# MCP794x-breakout.net
KiCad netlist of a schematic drawn in EAGLE
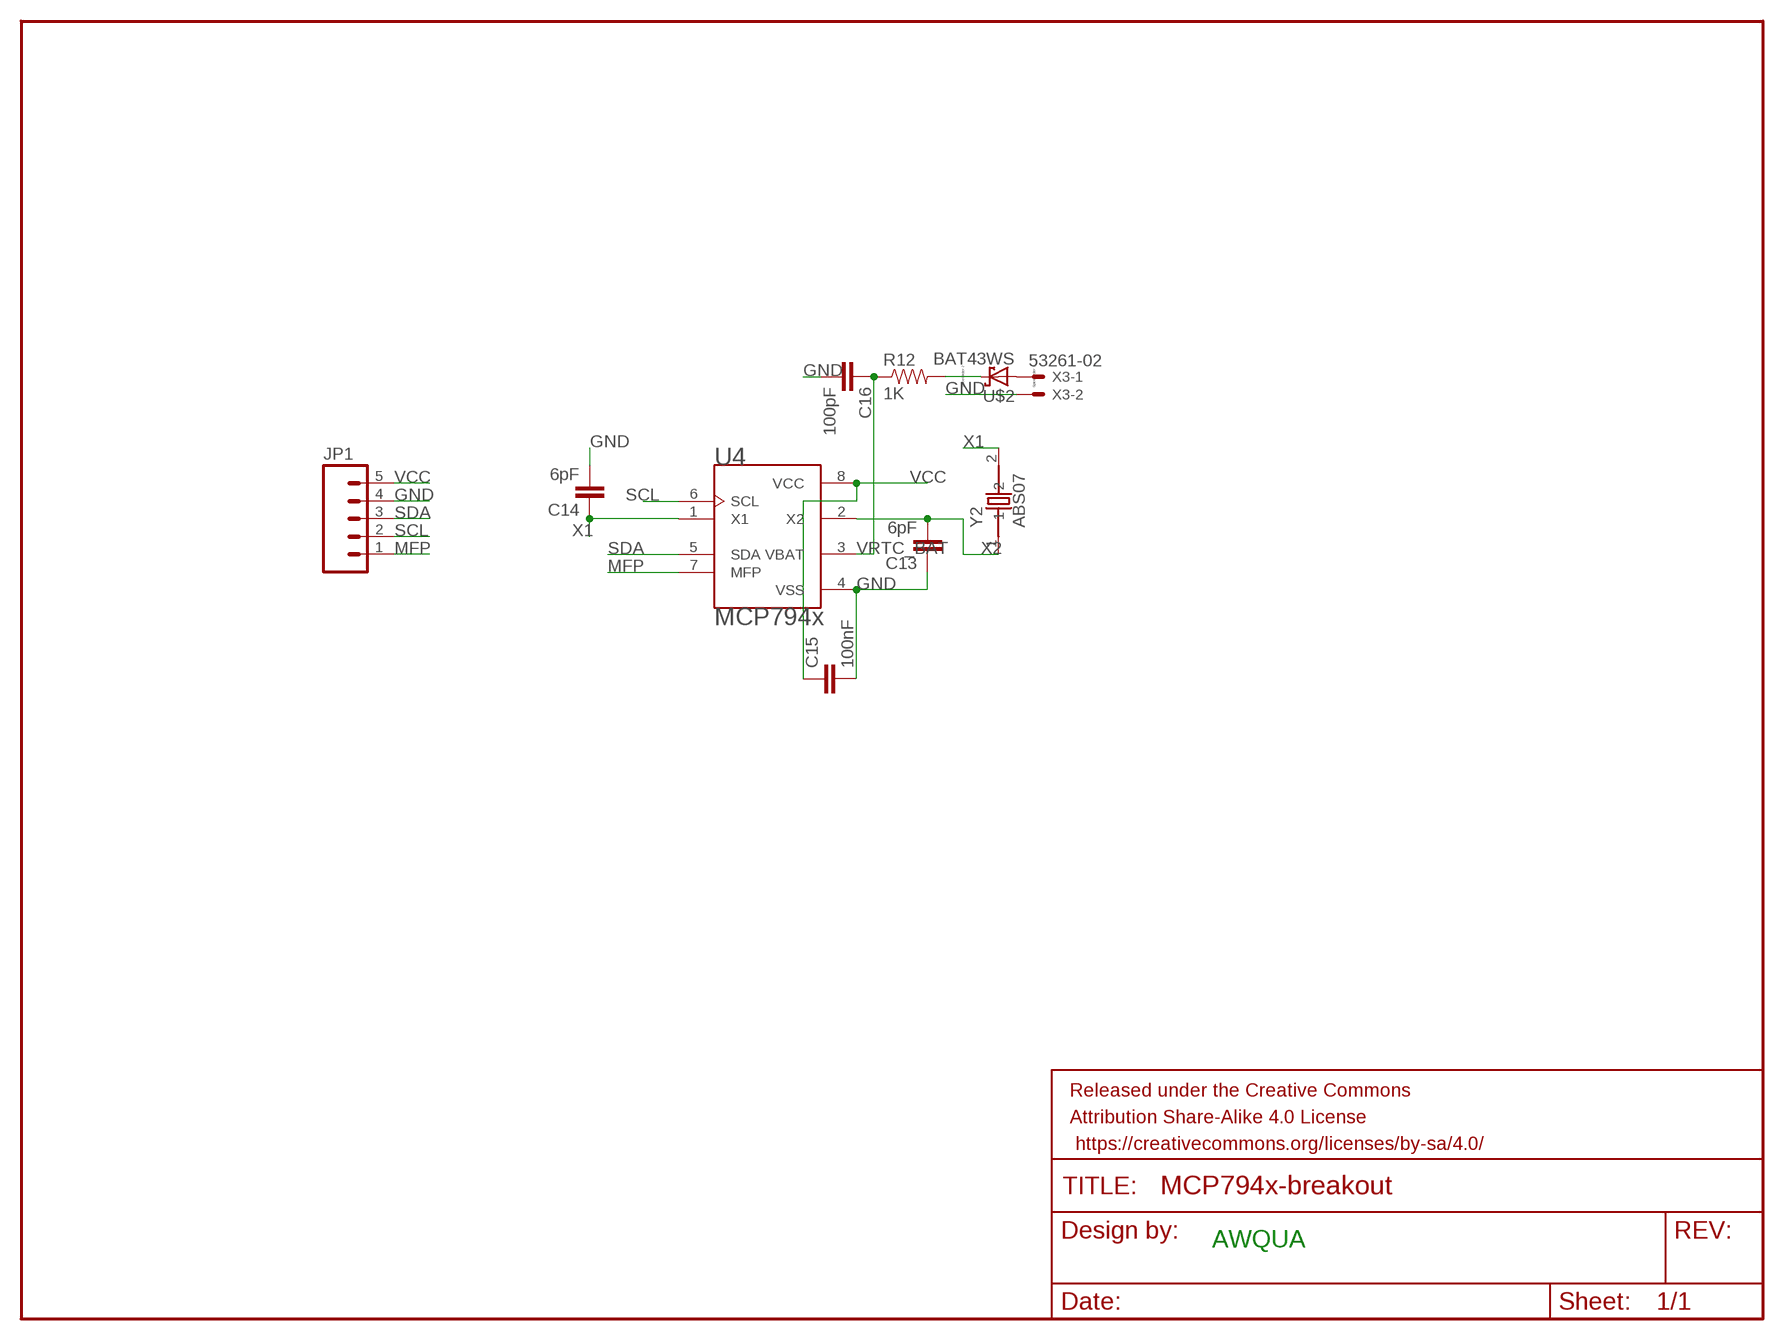
[diagram p0: schematic, sheet 1]

(export (version "E")
  (design (tool "Eeschema 10.0.6"))
  (components
    (comp (ref "C13")
      (value "6pF")
      (footprint "eagle-import:0603-CAP")
      (libsource (lib "eagle-import") (part "CAP0603-CAP"))
    )
    (comp (ref "C14")
      (value "6pF")
      (footprint "eagle-import:0603-CAP")
      (libsource (lib "eagle-import") (part "CAP0603-CAP"))
    )
    (comp (ref "C15")
      (value "100nF")
      (footprint "eagle-import:0603-CAP")
      (libsource (lib "eagle-import") (part "CAP0603-CAP"))
    )
    (comp (ref "C16")
      (value "100pF")
      (footprint "eagle-import:0603-CAP")
      (libsource (lib "eagle-import") (part "CAP0603-CAP"))
    )
    (comp (ref "FRAME1")
      (value "FRAME-LETTER")
      (footprint "eagle-import:CREATIVE_COMMONS")
      (libsource (lib "eagle-import") (part "FRAME-LETTER"))
    )
    (comp (ref "JP1")
      (value "M05PTH")
      (footprint "eagle-import:1X05")
      (libsource (lib "eagle-import") (part "M05PTH"))
    )
    (comp (ref "R12")
      (value "1K")
      (footprint "eagle-import:0603-RES")
      (libsource (lib "eagle-import") (part "RESISTOR0603-RES"))
    )
    (comp (ref "U$2")
      (value "BAT43WS")
      (footprint "eagle-import:BAT43WS")
      (libsource (lib "eagle-import") (part "BAT43WS"))
    )
    (comp (ref "U4")
      (value "MCP794x")
      (footprint "eagle-import:SOIC127P600X175-8N")
      (fields (field (name "MF") "Microchip") (field (name "MP") "MCP7940M-I/SN"))
      (libsource (lib "eagle-import") (part "MCP7940M-I/SN"))
    )
    (comp (ref "X3")
      (value "53261-02")
      (footprint "eagle-import:53261-02")
      (libsource (lib "eagle-import") (part "53?-02261"))
    )
    (comp (ref "Y2")
      (value "ABS07")
      (footprint "eagle-import:XTAL320X150X90")
      (fields (field (name "MF") "Abracon") (field (name "MP") "ABS07-32.768KHZ-T"))
      (libsource (lib "eagle-import") (part "ABS07-32.768KHZ-T"))
    )
  )
  (nets
    (net (code "1") (name "/GND") (class "Default")
      (node (ref "C13") (pin "1") (pinfunction "1_1") (pintype "passive"))
      (node (ref "C14") (pin "2") (pinfunction "2_2") (pintype "passive"))
      (node (ref "C15") (pin "2") (pinfunction "2_2") (pintype "passive"))
      (node (ref "C16") (pin "2") (pinfunction "2_2") (pintype "passive"))
      (node (ref "JP1") (pin "4") (pinfunction "4_4") (pintype "passive"))
      (node (ref "U4") (pin "4") (pinfunction "VSS_4") (pintype "passive"))
      (node (ref "X3") (pin "2") (pinfunction "S_2") (pintype "passive"))
    )
    (net (code "2") (name "/MFP") (class "Default")
      (node (ref "JP1") (pin "1") (pinfunction "1_1") (pintype "passive"))
      (node (ref "U4") (pin "7") (pinfunction "MFP_7") (pintype "bidirectional"))
    )
    (net (code "3") (name "/SCL") (class "Default")
      (node (ref "JP1") (pin "2") (pinfunction "2_2") (pintype "passive"))
      (node (ref "U4") (pin "6") (pinfunction "SCL_6") (pintype "input"))
    )
    (net (code "4") (name "/SDA") (class "Default")
      (node (ref "JP1") (pin "3") (pinfunction "3_3") (pintype "passive"))
      (node (ref "U4") (pin "5") (pinfunction "SDA_5") (pintype "bidirectional"))
    )
    (net (code "5") (name "/VCC") (class "Default")
      (node (ref "C15") (pin "1") (pinfunction "1_1") (pintype "passive"))
      (node (ref "JP1") (pin "5") (pinfunction "5_5") (pintype "passive"))
      (node (ref "U4") (pin "8") (pinfunction "VCC_8") (pintype "power_in"))
    )
    (net (code "6") (name "/VRTC_BAT") (class "Default")
      (node (ref "C16") (pin "1") (pinfunction "1_1") (pintype "passive"))
      (node (ref "R12") (pin "1") (pinfunction "1_1") (pintype "passive"))
      (node (ref "U4") (pin "3") (pinfunction "VBAT_3") (pintype "power_in"))
    )
    (net (code "7") (name "/X1") (class "Default")
      (node (ref "C14") (pin "1") (pinfunction "1_1") (pintype "passive"))
      (node (ref "U4") (pin "1") (pinfunction "X1_1") (pintype "input"))
      (node (ref "Y2") (pin "2") (pinfunction "2_2") (pintype "passive"))
    )
    (net (code "8") (name "/X2") (class "Default")
      (node (ref "C13") (pin "2") (pinfunction "2_2") (pintype "passive"))
      (node (ref "U4") (pin "2") (pinfunction "X2_2") (pintype "output"))
      (node (ref "Y2") (pin "1") (pinfunction "1_1") (pintype "passive"))
    )
    (net (code "9") (name "Net-(U$2-A)") (class "Default")
      (node (ref "R12") (pin "2") (pinfunction "2_2") (pintype "passive"))
      (node (ref "U$2") (pin "PIN2") (pinfunction "A_PIN2") (pintype "passive"))
    )
    (net (code "10") (name "Net-(U$2-C)") (class "Default")
      (node (ref "U$2") (pin "PIN1") (pinfunction "C_PIN1") (pintype "passive"))
      (node (ref "X3") (pin "1") (pinfunction "S_1") (pintype "passive"))
    )
  )
)
